# V2.net
KiCad netlist of a schematic drawn in Altium Designer
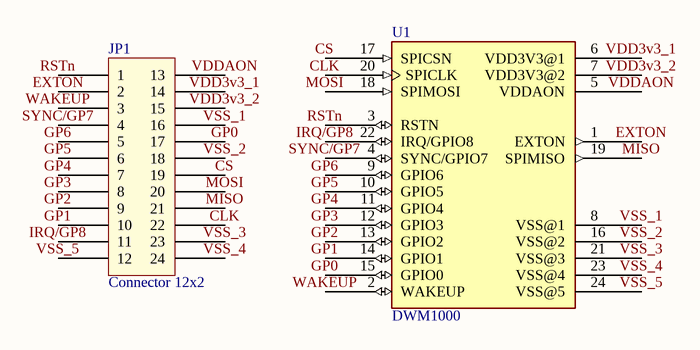
[diagram p0: V2.SchDoc]

(export (version "E")
  (design (tool "Eeschema 10.0.6"))
  (components
    (comp (ref "JP1")
      (value "Connector 12x2")
      (footprint "JP12X2_2")
      (libsource (lib "Cty1") (part "JP12x2"))
    )
    (comp (ref "U1")
      (value "DWM1000")
      (footprint "DW1000:XCVR_DWM1000")
      (description "802.15.4 IR-UWB Transceiver Module 3.5GHz ~ 6.5GHz Integrated, Chip Surface Mount")
      (fields (field (name "MF") "Decawave Limited"))
      (libsource (lib "DW1000") (part "DWM1000"))
    )
  )
  (nets
    (net (code "1") (name "/CLK") (class "Default")
      (node (ref "JP1") (pin "22") (pinfunction "22_22") (pintype "passive"))
      (node (ref "U1") (pin "20") (pinfunction "SPICLK_20") (pintype "input"))
    )
    (net (code "2") (name "/CS") (class "Default")
      (node (ref "JP1") (pin "19") (pinfunction "19_19") (pintype "passive"))
      (node (ref "U1") (pin "17") (pinfunction "SPICSN_17") (pintype "input"))
    )
    (net (code "3") (name "/EXTON") (class "Default")
      (node (ref "JP1") (pin "2") (pinfunction "2_2") (pintype "passive"))
      (node (ref "U1") (pin "1") (pinfunction "EXTON_1") (pintype "output"))
    )
    (net (code "4") (name "/GP0") (class "Default")
      (node (ref "JP1") (pin "17") (pinfunction "17_17") (pintype "passive"))
      (node (ref "U1") (pin "15") (pinfunction "GPIO0_15") (pintype "bidirectional"))
    )
    (net (code "5") (name "/GP1") (class "Default")
      (node (ref "JP1") (pin "10") (pinfunction "10_10") (pintype "passive"))
      (node (ref "U1") (pin "14") (pinfunction "GPIO1_14") (pintype "bidirectional"))
    )
    (net (code "6") (name "/GP2") (class "Default")
      (node (ref "JP1") (pin "9") (pinfunction "9_9") (pintype "passive"))
      (node (ref "U1") (pin "13") (pinfunction "GPIO2_13") (pintype "bidirectional"))
    )
    (net (code "7") (name "/GP3") (class "Default")
      (node (ref "JP1") (pin "8") (pinfunction "8_8") (pintype "passive"))
      (node (ref "U1") (pin "12") (pinfunction "GPIO3_12") (pintype "bidirectional"))
    )
    (net (code "8") (name "/GP4") (class "Default")
      (node (ref "JP1") (pin "7") (pinfunction "7_7") (pintype "passive"))
      (node (ref "U1") (pin "11") (pinfunction "GPIO4_11") (pintype "bidirectional"))
    )
    (net (code "9") (name "/GP5") (class "Default")
      (node (ref "JP1") (pin "6") (pinfunction "6_6") (pintype "passive"))
      (node (ref "U1") (pin "10") (pinfunction "GPIO5_10") (pintype "bidirectional"))
    )
    (net (code "10") (name "/GP6") (class "Default")
      (node (ref "JP1") (pin "5") (pinfunction "5_5") (pintype "passive"))
      (node (ref "U1") (pin "9") (pinfunction "GPIO6_9") (pintype "bidirectional"))
    )
    (net (code "11") (name "/IRQ{slash}GP8") (class "Default")
      (node (ref "JP1") (pin "11") (pinfunction "11_11") (pintype "passive"))
      (node (ref "U1") (pin "22") (pinfunction "IRQ/GPIO8_22") (pintype "bidirectional"))
    )
    (net (code "12") (name "/MISO") (class "Default")
      (node (ref "JP1") (pin "21") (pinfunction "21_21") (pintype "passive"))
      (node (ref "U1") (pin "19") (pinfunction "SPIMISO_19") (pintype "output"))
    )
    (net (code "13") (name "/MOSI") (class "Default")
      (node (ref "JP1") (pin "20") (pinfunction "20_20") (pintype "passive"))
      (node (ref "U1") (pin "18") (pinfunction "SPIMOSI_18") (pintype "input"))
    )
    (net (code "14") (name "/RSTn") (class "Default")
      (node (ref "JP1") (pin "1") (pinfunction "1_1") (pintype "passive"))
      (node (ref "U1") (pin "3") (pinfunction "RSTN_3") (pintype "bidirectional"))
    )
    (net (code "15") (name "/SYNC{slash}GP7") (class "Default")
      (node (ref "JP1") (pin "4") (pinfunction "4_4") (pintype "passive"))
      (node (ref "U1") (pin "4") (pinfunction "SYNC/GPIO7_4") (pintype "bidirectional"))
    )
    (net (code "16") (name "/VDD3v3_1") (class "Default")
      (node (ref "JP1") (pin "14") (pinfunction "14_14") (pintype "passive"))
      (node (ref "U1") (pin "6") (pinfunction "VDD3V3@1_6") (pintype "power_in"))
    )
    (net (code "17") (name "/VDD3v3_2") (class "Default")
      (node (ref "JP1") (pin "15") (pinfunction "15_15") (pintype "passive"))
      (node (ref "U1") (pin "7") (pinfunction "VDD3V3@2_7") (pintype "power_in"))
    )
    (net (code "18") (name "/VDDAON") (class "Default")
      (node (ref "JP1") (pin "13") (pinfunction "13_13") (pintype "passive"))
      (node (ref "U1") (pin "5") (pinfunction "VDDAON_5") (pintype "power_in"))
    )
    (net (code "19") (name "/VSS_1") (class "Default")
      (node (ref "JP1") (pin "16") (pinfunction "16_16") (pintype "passive"))
      (node (ref "U1") (pin "8") (pinfunction "VSS@1_8") (pintype "power_in"))
    )
    (net (code "20") (name "/VSS_2") (class "Default")
      (node (ref "JP1") (pin "18") (pinfunction "18_18") (pintype "passive"))
      (node (ref "U1") (pin "16") (pinfunction "VSS@2_16") (pintype "power_in"))
    )
    (net (code "21") (name "/VSS_3") (class "Default")
      (node (ref "JP1") (pin "23") (pinfunction "23_23") (pintype "passive"))
      (node (ref "U1") (pin "21") (pinfunction "VSS@3_21") (pintype "power_in"))
    )
    (net (code "22") (name "/VSS_4") (class "Default")
      (node (ref "JP1") (pin "24") (pinfunction "24_24") (pintype "passive"))
      (node (ref "U1") (pin "23") (pinfunction "VSS@4_23") (pintype "power_in"))
    )
    (net (code "23") (name "/VSS_5") (class "Default")
      (node (ref "JP1") (pin "12") (pinfunction "12_12") (pintype "passive"))
      (node (ref "U1") (pin "24") (pinfunction "VSS@5_24") (pintype "power_in"))
    )
    (net (code "24") (name "/WAKEUP") (class "Default")
      (node (ref "JP1") (pin "3") (pinfunction "3_3") (pintype "passive"))
      (node (ref "U1") (pin "2") (pinfunction "WAKEUP_2") (pintype "bidirectional"))
    )
  )
)
